# 06_LMS7002M_Power.net
KiCad netlist of a schematic drawn in Altium Designer
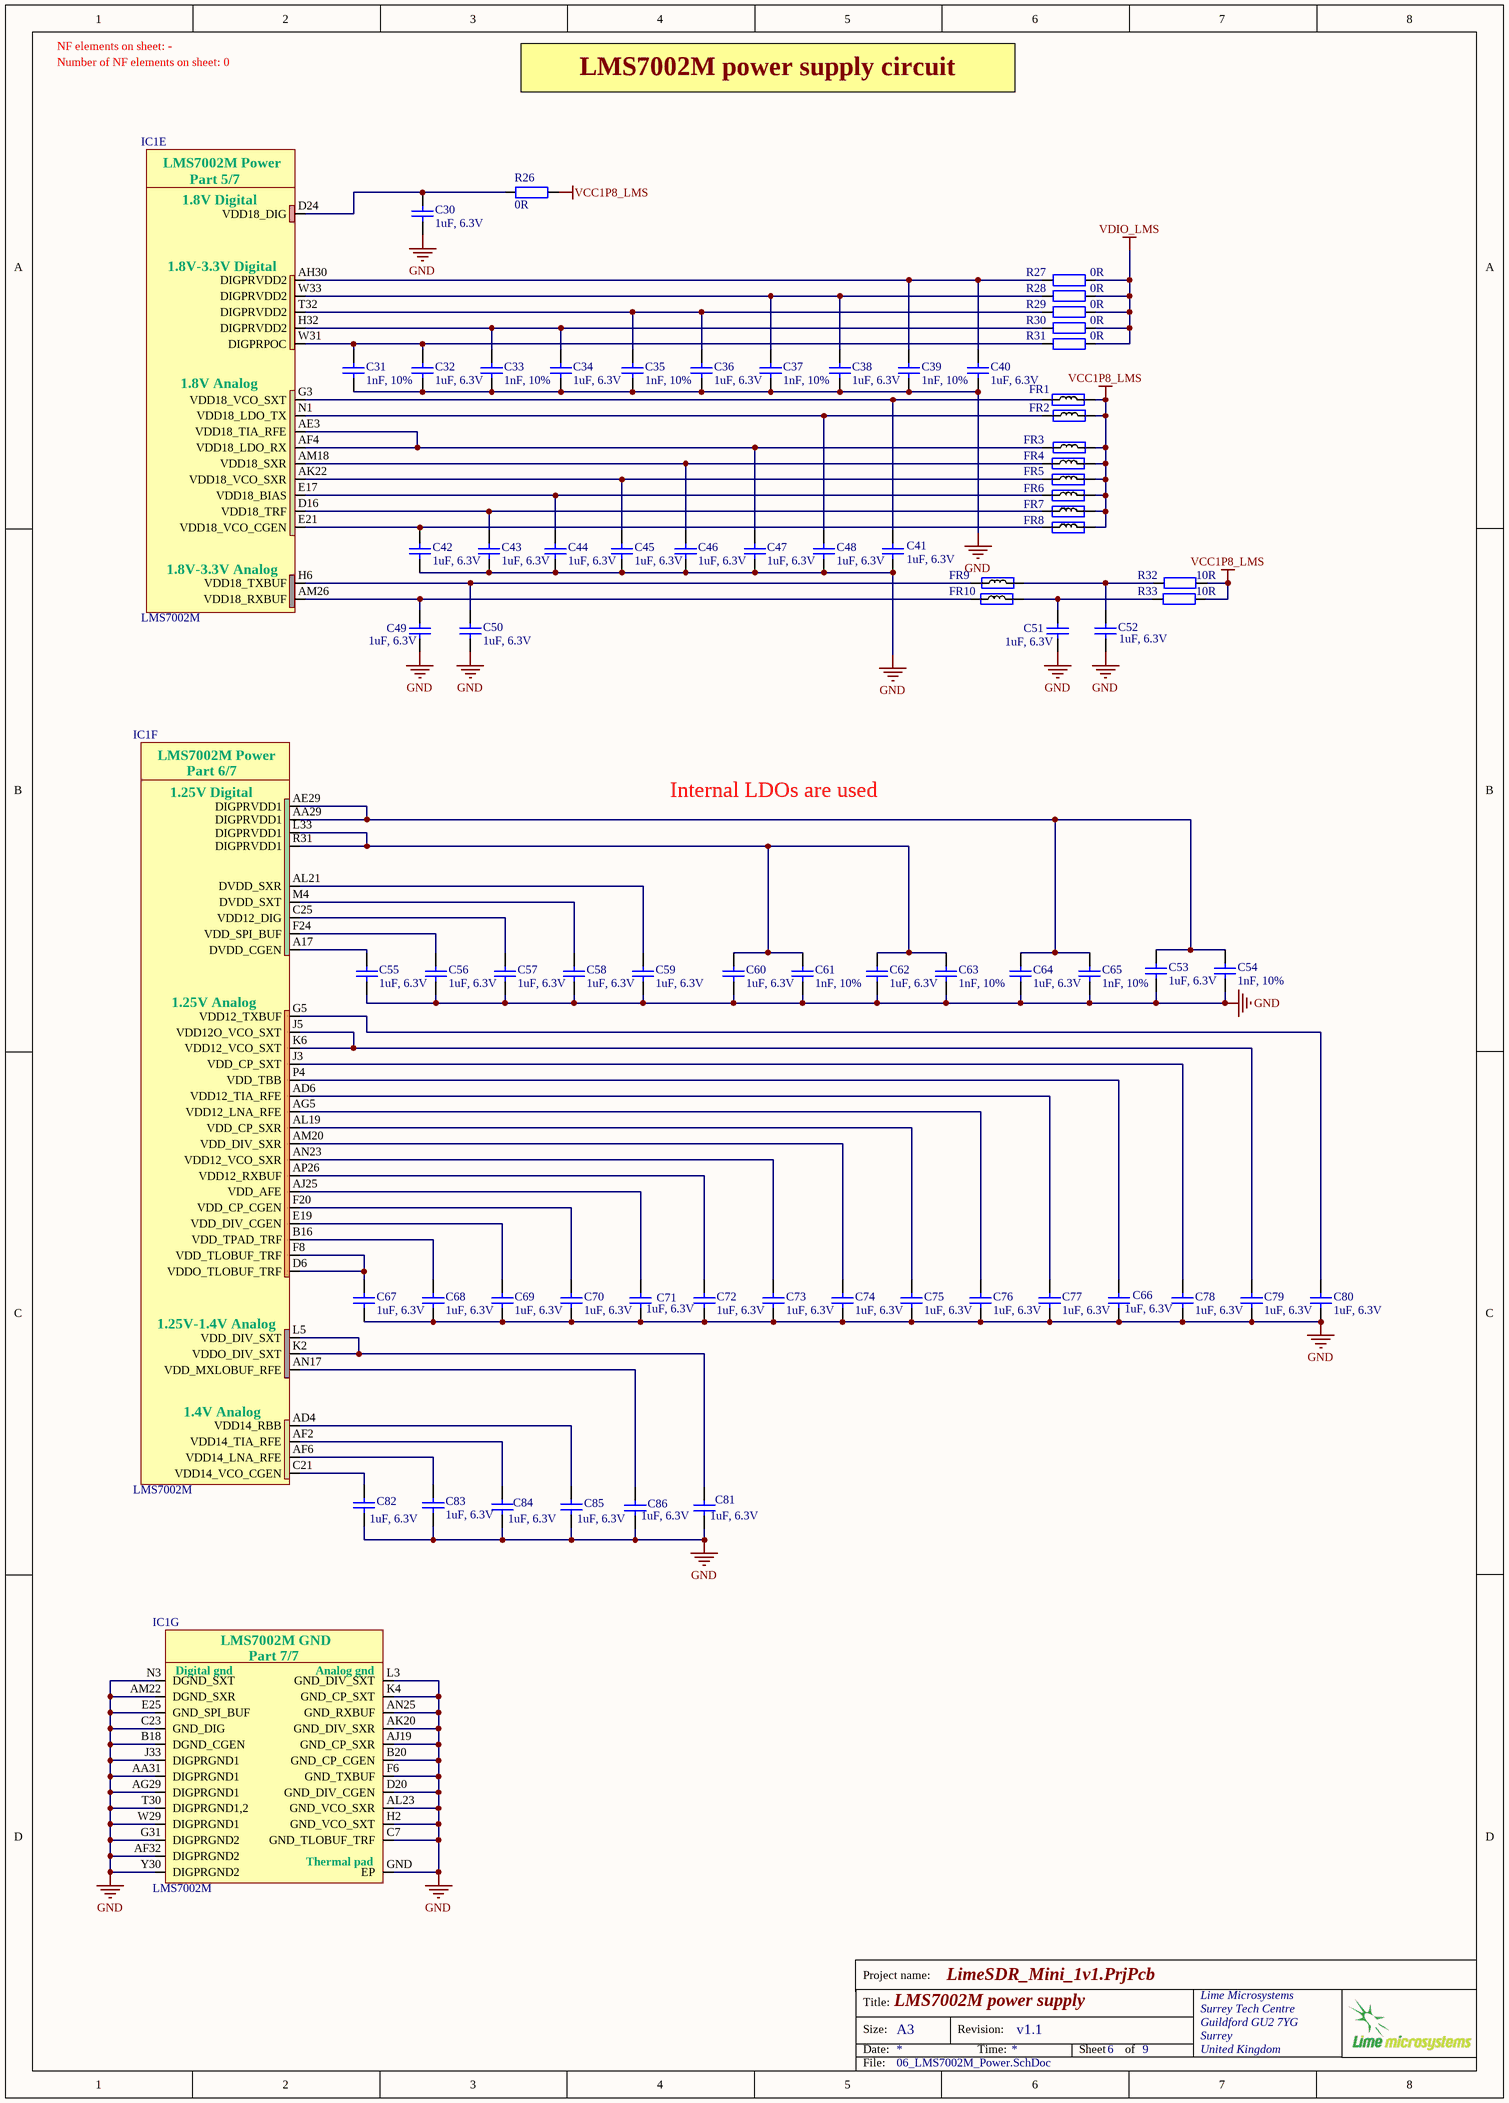
[diagram p0: 06_LMS7002M_Power.SchDoc]

(export (version "E")
  (design (tool "Eeschema 10.0.6"))
  (components
    (comp (ref "C30")
      (value "1uF, 6.3V")
      (footprint "CAP0201")
      (fields (field (name "TOLERANCE") "±20%") (field (name "MANUFACTURER") "TDK Corporation"))
      (libsource (lib "LimeMicroAltiumLib_schLib") (part "Cap_0402"))
    )
    (comp (ref "C31")
      (value "1nF, 10%")
      (footprint "CAP0201")
      (fields (field (name "TOLERANCE") "±10%") (field (name "MANUFACTURER") "TDK Corporation"))
      (libsource (lib "LimeMicroAltiumLib_schLib") (part "Cap_0402"))
    )
    (comp (ref "C32")
      (value "1uF, 6.3V")
      (footprint "CAP0201")
      (fields (field (name "TOLERANCE") "±20%") (field (name "MANUFACTURER") "TDK Corporation"))
      (libsource (lib "LimeMicroAltiumLib_schLib") (part "Cap_0402"))
    )
    (comp (ref "C33")
      (value "1nF, 10%")
      (footprint "CAP0201")
      (fields (field (name "TOLERANCE") "±10%") (field (name "MANUFACTURER") "TDK Corporation"))
      (libsource (lib "LimeMicroAltiumLib_schLib") (part "Cap_0402"))
    )
    (comp (ref "C34")
      (value "1uF, 6.3V")
      (footprint "CAP0201")
      (fields (field (name "TOLERANCE") "±20%") (field (name "MANUFACTURER") "TDK Corporation"))
      (libsource (lib "LimeMicroAltiumLib_schLib") (part "Cap_0402"))
    )
    (comp (ref "C35")
      (value "1nF, 10%")
      (footprint "CAP0201")
      (fields (field (name "TOLERANCE") "±10%") (field (name "MANUFACTURER") "TDK Corporation"))
      (libsource (lib "LimeMicroAltiumLib_schLib") (part "Cap_0402"))
    )
    (comp (ref "C36")
      (value "1uF, 6.3V")
      (footprint "CAP0201")
      (fields (field (name "TOLERANCE") "±20%") (field (name "MANUFACTURER") "TDK Corporation"))
      (libsource (lib "LimeMicroAltiumLib_schLib") (part "Cap_0402"))
    )
    (comp (ref "C37")
      (value "1nF, 10%")
      (footprint "CAP0201")
      (fields (field (name "TOLERANCE") "±10%") (field (name "MANUFACTURER") "TDK Corporation"))
      (libsource (lib "LimeMicroAltiumLib_schLib") (part "Cap_0402"))
    )
    (comp (ref "C38")
      (value "1uF, 6.3V")
      (footprint "CAP0201")
      (fields (field (name "TOLERANCE") "±20%") (field (name "MANUFACTURER") "TDK Corporation"))
      (libsource (lib "LimeMicroAltiumLib_schLib") (part "Cap_0402"))
    )
    (comp (ref "C39")
      (value "1nF, 10%")
      (footprint "CAP0201")
      (fields (field (name "TOLERANCE") "±10%") (field (name "MANUFACTURER") "TDK Corporation"))
      (libsource (lib "LimeMicroAltiumLib_schLib") (part "Cap_0402"))
    )
    (comp (ref "C40")
      (value "1uF, 6.3V")
      (footprint "CAP0201")
      (fields (field (name "TOLERANCE") "±20%") (field (name "MANUFACTURER") "TDK Corporation"))
      (libsource (lib "LimeMicroAltiumLib_schLib") (part "Cap_0402"))
    )
    (comp (ref "C41")
      (value "1uF, 6.3V")
      (footprint "CAP0201")
      (fields (field (name "TOLERANCE") "±20%") (field (name "MANUFACTURER") "TDK Corporation"))
      (libsource (lib "LimeMicroAltiumLib_schLib") (part "Cap_0402"))
    )
    (comp (ref "C42")
      (value "1uF, 6.3V")
      (footprint "CAP0201")
      (fields (field (name "TOLERANCE") "±20%") (field (name "MANUFACTURER") "TDK Corporation"))
      (libsource (lib "LimeMicroAltiumLib_schLib") (part "Cap_0402"))
    )
    (comp (ref "C43")
      (value "1uF, 6.3V")
      (footprint "CAP0201")
      (fields (field (name "TOLERANCE") "±20%") (field (name "MANUFACTURER") "TDK Corporation"))
      (libsource (lib "LimeMicroAltiumLib_schLib") (part "Cap_0402"))
    )
    (comp (ref "C44")
      (value "1uF, 6.3V")
      (footprint "CAP0201")
      (fields (field (name "TOLERANCE") "±20%") (field (name "MANUFACTURER") "TDK Corporation"))
      (libsource (lib "LimeMicroAltiumLib_schLib") (part "Cap_0402"))
    )
    (comp (ref "C45")
      (value "1uF, 6.3V")
      (footprint "CAP0201")
      (fields (field (name "TOLERANCE") "±20%") (field (name "MANUFACTURER") "TDK Corporation"))
      (libsource (lib "LimeMicroAltiumLib_schLib") (part "Cap_0402"))
    )
    (comp (ref "C46")
      (value "1uF, 6.3V")
      (footprint "CAP0201")
      (fields (field (name "TOLERANCE") "±20%") (field (name "MANUFACTURER") "TDK Corporation"))
      (libsource (lib "LimeMicroAltiumLib_schLib") (part "Cap_0402"))
    )
    (comp (ref "C47")
      (value "1uF, 6.3V")
      (footprint "CAP0201")
      (fields (field (name "TOLERANCE") "±20%") (field (name "MANUFACTURER") "TDK Corporation"))
      (libsource (lib "LimeMicroAltiumLib_schLib") (part "Cap_0402"))
    )
    (comp (ref "C48")
      (value "1uF, 6.3V")
      (footprint "CAP0201")
      (fields (field (name "TOLERANCE") "±20%") (field (name "MANUFACTURER") "TDK Corporation"))
      (libsource (lib "LimeMicroAltiumLib_schLib") (part "Cap_0402"))
    )
    (comp (ref "C49")
      (value "1uF, 6.3V")
      (footprint "CAP0201")
      (fields (field (name "TOLERANCE") "±20%") (field (name "MANUFACTURER") "TDK Corporation"))
      (libsource (lib "LimeMicroAltiumLib_schLib") (part "Cap_0402"))
    )
    (comp (ref "C50")
      (value "1uF, 6.3V")
      (footprint "CAP0201")
      (fields (field (name "TOLERANCE") "±20%") (field (name "MANUFACTURER") "TDK Corporation"))
      (libsource (lib "LimeMicroAltiumLib_schLib") (part "Cap_0402"))
    )
    (comp (ref "C51")
      (value "1uF, 6.3V")
      (footprint "CAP0201")
      (fields (field (name "TOLERANCE") "±20%") (field (name "MANUFACTURER") "TDK Corporation"))
      (libsource (lib "LimeMicroAltiumLib_schLib") (part "Cap_0402"))
    )
    (comp (ref "C52")
      (value "1uF, 6.3V")
      (footprint "CAP0201")
      (fields (field (name "TOLERANCE") "±20%") (field (name "MANUFACTURER") "TDK Corporation"))
      (libsource (lib "LimeMicroAltiumLib_schLib") (part "Cap_0402"))
    )
    (comp (ref "C53")
      (value "1uF, 6.3V")
      (footprint "CAP0201")
      (fields (field (name "TOLERANCE") "±20%") (field (name "MANUFACTURER") "TDK Corporation"))
      (libsource (lib "LimeMicroAltiumLib_schLib") (part "Cap_0402"))
    )
    (comp (ref "C54")
      (value "1nF, 10%")
      (footprint "CAP0201")
      (fields (field (name "TOLERANCE") "±10%") (field (name "MANUFACTURER") "TDK Corporation"))
      (libsource (lib "LimeMicroAltiumLib_schLib") (part "Cap_0402"))
    )
    (comp (ref "C55")
      (value "1uF, 6.3V")
      (footprint "CAP0201")
      (fields (field (name "TOLERANCE") "±20%") (field (name "MANUFACTURER") "TDK Corporation"))
      (libsource (lib "LimeMicroAltiumLib_schLib") (part "Cap_0402"))
    )
    (comp (ref "C56")
      (value "1uF, 6.3V")
      (footprint "CAP0201")
      (fields (field (name "TOLERANCE") "±20%") (field (name "MANUFACTURER") "TDK Corporation"))
      (libsource (lib "LimeMicroAltiumLib_schLib") (part "Cap_0402"))
    )
    (comp (ref "C57")
      (value "1uF, 6.3V")
      (footprint "CAP0201")
      (fields (field (name "TOLERANCE") "±20%") (field (name "MANUFACTURER") "TDK Corporation"))
      (libsource (lib "LimeMicroAltiumLib_schLib") (part "Cap_0402"))
    )
    (comp (ref "C58")
      (value "1uF, 6.3V")
      (footprint "CAP0201")
      (fields (field (name "TOLERANCE") "±20%") (field (name "MANUFACTURER") "TDK Corporation"))
      (libsource (lib "LimeMicroAltiumLib_schLib") (part "Cap_0402"))
    )
    (comp (ref "C59")
      (value "1uF, 6.3V")
      (footprint "CAP0201")
      (fields (field (name "TOLERANCE") "±20%") (field (name "MANUFACTURER") "TDK Corporation"))
      (libsource (lib "LimeMicroAltiumLib_schLib") (part "Cap_0402"))
    )
    (comp (ref "C60")
      (value "1uF, 6.3V")
      (footprint "CAP0201")
      (fields (field (name "TOLERANCE") "±20%") (field (name "MANUFACTURER") "TDK Corporation"))
      (libsource (lib "LimeMicroAltiumLib_schLib") (part "Cap_0402"))
    )
    (comp (ref "C61")
      (value "1nF, 10%")
      (footprint "CAP0201")
      (fields (field (name "TOLERANCE") "±10%") (field (name "MANUFACTURER") "TDK Corporation"))
      (libsource (lib "LimeMicroAltiumLib_schLib") (part "Cap_0402"))
    )
    (comp (ref "C62")
      (value "1uF, 6.3V")
      (footprint "CAP0201")
      (fields (field (name "TOLERANCE") "±20%") (field (name "MANUFACTURER") "TDK Corporation"))
      (libsource (lib "LimeMicroAltiumLib_schLib") (part "Cap_0402"))
    )
    (comp (ref "C63")
      (value "1nF, 10%")
      (footprint "CAP0201")
      (fields (field (name "TOLERANCE") "±10%") (field (name "MANUFACTURER") "TDK Corporation"))
      (libsource (lib "LimeMicroAltiumLib_schLib") (part "Cap_0402"))
    )
    (comp (ref "C64")
      (value "1uF, 6.3V")
      (footprint "CAP0201")
      (fields (field (name "TOLERANCE") "±20%") (field (name "MANUFACTURER") "TDK Corporation"))
      (libsource (lib "LimeMicroAltiumLib_schLib") (part "Cap_0402"))
    )
    (comp (ref "C65")
      (value "1nF, 10%")
      (footprint "CAP0201")
      (fields (field (name "TOLERANCE") "±10%") (field (name "MANUFACTURER") "TDK Corporation"))
      (libsource (lib "LimeMicroAltiumLib_schLib") (part "Cap_0402"))
    )
    (comp (ref "C66")
      (value "1uF, 6.3V")
      (footprint "CAP0201")
      (fields (field (name "TOLERANCE") "±20%") (field (name "MANUFACTURER") "TDK Corporation"))
      (libsource (lib "LimeMicroAltiumLib_schLib") (part "Cap_0402"))
    )
    (comp (ref "C67")
      (value "1uF, 6.3V")
      (footprint "CAP0201")
      (fields (field (name "TOLERANCE") "±20%") (field (name "MANUFACTURER") "TDK Corporation"))
      (libsource (lib "LimeMicroAltiumLib_schLib") (part "Cap_0402"))
    )
    (comp (ref "C68")
      (value "1uF, 6.3V")
      (footprint "CAP0201")
      (fields (field (name "TOLERANCE") "±20%") (field (name "MANUFACTURER") "TDK Corporation"))
      (libsource (lib "LimeMicroAltiumLib_schLib") (part "Cap_0402"))
    )
    (comp (ref "C69")
      (value "1uF, 6.3V")
      (footprint "CAP0201")
      (fields (field (name "TOLERANCE") "±20%") (field (name "MANUFACTURER") "TDK Corporation"))
      (libsource (lib "LimeMicroAltiumLib_schLib") (part "Cap_0402"))
    )
    (comp (ref "C70")
      (value "1uF, 6.3V")
      (footprint "CAP0201")
      (fields (field (name "TOLERANCE") "±20%") (field (name "MANUFACTURER") "TDK Corporation"))
      (libsource (lib "LimeMicroAltiumLib_schLib") (part "Cap_0402"))
    )
    (comp (ref "C71")
      (value "1uF, 6.3V")
      (footprint "CAP0201")
      (fields (field (name "TOLERANCE") "±20%") (field (name "MANUFACTURER") "TDK Corporation"))
      (libsource (lib "LimeMicroAltiumLib_schLib") (part "Cap_0402"))
    )
    (comp (ref "C72")
      (value "1uF, 6.3V")
      (footprint "CAP0201")
      (fields (field (name "TOLERANCE") "±20%") (field (name "MANUFACTURER") "TDK Corporation"))
      (libsource (lib "LimeMicroAltiumLib_schLib") (part "Cap_0402"))
    )
    (comp (ref "C73")
      (value "1uF, 6.3V")
      (footprint "CAP0201")
      (fields (field (name "TOLERANCE") "±20%") (field (name "MANUFACTURER") "TDK Corporation"))
      (libsource (lib "LimeMicroAltiumLib_schLib") (part "Cap_0402"))
    )
    (comp (ref "C74")
      (value "1uF, 6.3V")
      (footprint "CAP0201")
      (fields (field (name "TOLERANCE") "±20%") (field (name "MANUFACTURER") "TDK Corporation"))
      (libsource (lib "LimeMicroAltiumLib_schLib") (part "Cap_0402"))
    )
    (comp (ref "C75")
      (value "1uF, 6.3V")
      (footprint "CAP0201")
      (fields (field (name "TOLERANCE") "±20%") (field (name "MANUFACTURER") "TDK Corporation"))
      (libsource (lib "LimeMicroAltiumLib_schLib") (part "Cap_0402"))
    )
    (comp (ref "C76")
      (value "1uF, 6.3V")
      (footprint "CAP0201")
      (fields (field (name "TOLERANCE") "±20%") (field (name "MANUFACTURER") "TDK Corporation"))
      (libsource (lib "LimeMicroAltiumLib_schLib") (part "Cap_0402"))
    )
    (comp (ref "C77")
      (value "1uF, 6.3V")
      (footprint "CAP0201")
      (fields (field (name "TOLERANCE") "±20%") (field (name "MANUFACTURER") "TDK Corporation"))
      (libsource (lib "LimeMicroAltiumLib_schLib") (part "Cap_0402"))
    )
    (comp (ref "C78")
      (value "1uF, 6.3V")
      (footprint "CAP0201")
      (fields (field (name "TOLERANCE") "±20%") (field (name "MANUFACTURER") "TDK Corporation"))
      (libsource (lib "LimeMicroAltiumLib_schLib") (part "Cap_0402"))
    )
    (comp (ref "C79")
      (value "1uF, 6.3V")
      (footprint "CAP0201")
      (fields (field (name "TOLERANCE") "±20%") (field (name "MANUFACTURER") "TDK Corporation"))
      (libsource (lib "LimeMicroAltiumLib_schLib") (part "Cap_0402"))
    )
    (comp (ref "C80")
      (value "1uF, 6.3V")
      (footprint "CAP0201")
      (fields (field (name "TOLERANCE") "±20%") (field (name "MANUFACTURER") "TDK Corporation"))
      (libsource (lib "LimeMicroAltiumLib_schLib") (part "Cap_0402"))
    )
    (comp (ref "C81")
      (value "1uF, 6.3V")
      (footprint "CAP0201")
      (fields (field (name "TOLERANCE") "±20%") (field (name "MANUFACTURER") "TDK Corporation"))
      (libsource (lib "LimeMicroAltiumLib_schLib") (part "Cap_0402"))
    )
    (comp (ref "C82")
      (value "1uF, 6.3V")
      (footprint "CAP0201")
      (fields (field (name "TOLERANCE") "±20%") (field (name "MANUFACTURER") "TDK Corporation"))
      (libsource (lib "LimeMicroAltiumLib_schLib") (part "Cap_0402"))
    )
    (comp (ref "C83")
      (value "1uF, 6.3V")
      (footprint "CAP0201")
      (fields (field (name "TOLERANCE") "±20%") (field (name "MANUFACTURER") "TDK Corporation"))
      (libsource (lib "LimeMicroAltiumLib_schLib") (part "Cap_0402"))
    )
    (comp (ref "C84")
      (value "1uF, 6.3V")
      (footprint "CAP0201")
      (fields (field (name "TOLERANCE") "±20%") (field (name "MANUFACTURER") "TDK Corporation"))
      (libsource (lib "LimeMicroAltiumLib_schLib") (part "Cap_0402"))
    )
    (comp (ref "C85")
      (value "1uF, 6.3V")
      (footprint "CAP0201")
      (fields (field (name "TOLERANCE") "±20%") (field (name "MANUFACTURER") "TDK Corporation"))
      (libsource (lib "LimeMicroAltiumLib_schLib") (part "Cap_0402"))
    )
    (comp (ref "C86")
      (value "1uF, 6.3V")
      (footprint "CAP0201")
      (fields (field (name "TOLERANCE") "±20%") (field (name "MANUFACTURER") "TDK Corporation"))
      (libsource (lib "LimeMicroAltiumLib_schLib") (part "Cap_0402"))
    )
    (comp (ref "FR1")
      (value "600R, 0.27A")
      (footprint "RES0201")
      (fields (field (name "MANUFACTURER") "Taiyo Yuden"))
      (libsource (lib "LimeMicroAltiumLib_schLib") (part "Ferrite"))
    )
    (comp (ref "FR2")
      (value "600R, 0.27A")
      (footprint "RES0201")
      (fields (field (name "MANUFACTURER") "Taiyo Yuden"))
      (libsource (lib "") (part "Ferrite_1"))
    )
    (comp (ref "FR3")
      (value "600R, 0.27A")
      (footprint "RES0201")
      (fields (field (name "MANUFACTURER") "Taiyo Yuden"))
      (libsource (lib "") (part "Ferrite_1"))
    )
    (comp (ref "FR4")
      (value "600R, 0.27A")
      (footprint "RES0201")
      (fields (field (name "MANUFACTURER") "Taiyo Yuden"))
      (libsource (lib "LimeMicroAltiumLib_schLib") (part "Ferrite"))
    )
    (comp (ref "FR5")
      (value "600R, 0.27A")
      (footprint "RES0201")
      (fields (field (name "MANUFACTURER") "Taiyo Yuden"))
      (libsource (lib "LimeMicroAltiumLib_schLib") (part "Ferrite"))
    )
    (comp (ref "FR6")
      (value "600R, 0.27A")
      (footprint "RES0201")
      (fields (field (name "MANUFACTURER") "Taiyo Yuden"))
      (libsource (lib "LimeMicroAltiumLib_schLib") (part "Ferrite"))
    )
    (comp (ref "FR7")
      (value "600R, 0.27A")
      (footprint "RES0201")
      (fields (field (name "MANUFACTURER") "Taiyo Yuden"))
      (libsource (lib "LimeMicroAltiumLib_schLib") (part "Ferrite"))
    )
    (comp (ref "FR8")
      (value "600R, 0.27A")
      (footprint "RES0201")
      (fields (field (name "MANUFACTURER") "Taiyo Yuden"))
      (libsource (lib "LimeMicroAltiumLib_schLib") (part "Ferrite"))
    )
    (comp (ref "FR9")
      (value "600R, 0.27A")
      (footprint "RES0201")
      (fields (field (name "MANUFACTURER") "Taiyo Yuden"))
      (libsource (lib "") (part "Ferrite_1"))
    )
    (comp (ref "FR10")
      (value "600R, 0.27A")
      (footprint "RES0201")
      (fields (field (name "MANUFACTURER") "Taiyo Yuden"))
      (libsource (lib "LimeMicroAltiumLib_schLib") (part "Ferrite"))
    )
    (comp (ref "IC1")
      (value "LMS7002M")
      (footprint "LMS7002M_v5_1")
      (description "Schematic symbol revision 3. Default footprint - 0.31mm pad")
      (fields (field (name "MANUFACTURER") "Lime Microsystems"))
      (libsource (lib "LimeMicroAltiumLib_schLib") (part "LMS7002Mr3"))
    )
    (comp (ref "R26")
      (value "0R")
      (footprint "RES0201")
      (fields (field (name "MANUFACTURER") "Rohm Semiconductor") (field (name "TOLERANCE") "Jumper"))
      (libsource (lib "LimeMicroAltiumLib_schLib") (part "Res_0402"))
    )
    (comp (ref "R27")
      (value "0R")
      (footprint "RES0402")
      (fields (field (name "MANUFACTURER") "Yageo") (field (name "TOLERANCE") "Jumper"))
      (libsource (lib "LimeMicroAltiumLib_schLib") (part "Res_0402"))
    )
    (comp (ref "R28")
      (value "0R")
      (footprint "RES0402")
      (fields (field (name "MANUFACTURER") "Yageo") (field (name "TOLERANCE") "Jumper"))
      (libsource (lib "LimeMicroAltiumLib_schLib") (part "Res_0402"))
    )
    (comp (ref "R29")
      (value "0R")
      (footprint "RES0402")
      (fields (field (name "MANUFACTURER") "Yageo") (field (name "TOLERANCE") "Jumper"))
      (libsource (lib "LimeMicroAltiumLib_schLib") (part "Res_0402"))
    )
    (comp (ref "R30")
      (value "0R")
      (footprint "RES0402")
      (fields (field (name "MANUFACTURER") "Yageo") (field (name "TOLERANCE") "Jumper"))
      (libsource (lib "LimeMicroAltiumLib_schLib") (part "Res_0402"))
    )
    (comp (ref "R31")
      (value "0R")
      (footprint "RES0402")
      (fields (field (name "MANUFACTURER") "Yageo") (field (name "TOLERANCE") "Jumper"))
      (libsource (lib "LimeMicroAltiumLib_schLib") (part "Res_0402"))
    )
    (comp (ref "R32")
      (value "10R")
      (footprint "RES0201")
      (fields
        (field (name "MANUFACTURER") "Panasonic Electronic Components")
        (field (name "TOLERANCE") "±1%")
        (field (name "MANUFACTURER PART NUMBER") "ERJ-1GEF10R0C")
      )
      (libsource (lib "LimeMicroAltiumLib_schLib") (part "Res_0402"))
    )
    (comp (ref "R33")
      (value "10R")
      (footprint "RES0201")
      (fields
        (field (name "MANUFACTURER") "Panasonic Electronic Components")
        (field (name "TOLERANCE") "±1%")
        (field (name "MANUFACTURER PART NUMBER") "ERJ-1GEF10R0C")
      )
      (libsource (lib "LimeMicroAltiumLib_schLib") (part "Res_0402"))
    )
  )
  (nets
    (net (code "1") (name "GND") (class "Default")
      (node (ref "C30") (pin "2") (pinfunction "2_2") (pintype "passive"))
      (node (ref "C31") (pin "2") (pinfunction "2_2") (pintype "passive"))
      (node (ref "C32") (pin "2") (pinfunction "2_2") (pintype "passive"))
      (node (ref "C33") (pin "2") (pinfunction "2_2") (pintype "passive"))
      (node (ref "C34") (pin "2") (pinfunction "2_2") (pintype "passive"))
      (node (ref "C35") (pin "2") (pinfunction "2_2") (pintype "passive"))
      (node (ref "C36") (pin "2") (pinfunction "2_2") (pintype "passive"))
      (node (ref "C37") (pin "2") (pinfunction "2_2") (pintype "passive"))
      (node (ref "C38") (pin "2") (pinfunction "2_2") (pintype "passive"))
      (node (ref "C39") (pin "2") (pinfunction "2_2") (pintype "passive"))
      (node (ref "C40") (pin "2") (pinfunction "2_2") (pintype "passive"))
      (node (ref "C41") (pin "2") (pinfunction "2_2") (pintype "passive"))
      (node (ref "C42") (pin "2") (pinfunction "2_2") (pintype "passive"))
      (node (ref "C43") (pin "2") (pinfunction "2_2") (pintype "passive"))
      (node (ref "C44") (pin "2") (pinfunction "2_2") (pintype "passive"))
      (node (ref "C45") (pin "2") (pinfunction "2_2") (pintype "passive"))
      (node (ref "C46") (pin "2") (pinfunction "2_2") (pintype "passive"))
      (node (ref "C47") (pin "2") (pinfunction "2_2") (pintype "passive"))
      (node (ref "C48") (pin "2") (pinfunction "2_2") (pintype "passive"))
      (node (ref "C49") (pin "2") (pinfunction "2_2") (pintype "passive"))
      (node (ref "C50") (pin "2") (pinfunction "2_2") (pintype "passive"))
      (node (ref "C51") (pin "2") (pinfunction "2_2") (pintype "passive"))
      (node (ref "C52") (pin "2") (pinfunction "2_2") (pintype "passive"))
      (node (ref "C53") (pin "2") (pinfunction "2_2") (pintype "passive"))
      (node (ref "C54") (pin "2") (pinfunction "2_2") (pintype "passive"))
      (node (ref "C55") (pin "2") (pinfunction "2_2") (pintype "passive"))
      (node (ref "C56") (pin "2") (pinfunction "2_2") (pintype "passive"))
      (node (ref "C57") (pin "2") (pinfunction "2_2") (pintype "passive"))
      (node (ref "C58") (pin "1") (pinfunction "1_1") (pintype "passive"))
      (node (ref "C59") (pin "2") (pinfunction "2_2") (pintype "passive"))
      (node (ref "C60") (pin "2") (pinfunction "2_2") (pintype "passive"))
      (node (ref "C61") (pin "2") (pinfunction "2_2") (pintype "passive"))
      (node (ref "C62") (pin "2") (pinfunction "2_2") (pintype "passive"))
      (node (ref "C63") (pin "2") (pinfunction "2_2") (pintype "passive"))
      (node (ref "C64") (pin "2") (pinfunction "2_2") (pintype "passive"))
      (node (ref "C65") (pin "2") (pinfunction "2_2") (pintype "passive"))
      (node (ref "C66") (pin "2") (pinfunction "2_2") (pintype "passive"))
      (node (ref "C67") (pin "2") (pinfunction "2_2") (pintype "passive"))
      (node (ref "C68") (pin "2") (pinfunction "2_2") (pintype "passive"))
      (node (ref "C69") (pin "2") (pinfunction "2_2") (pintype "passive"))
      (node (ref "C70") (pin "1") (pinfunction "1_1") (pintype "passive"))
      (node (ref "C71") (pin "2") (pinfunction "2_2") (pintype "passive"))
      (node (ref "C72") (pin "2") (pinfunction "2_2") (pintype "passive"))
      (node (ref "C73") (pin "2") (pinfunction "2_2") (pintype "passive"))
      (node (ref "C74") (pin "2") (pinfunction "2_2") (pintype "passive"))
      (node (ref "C75") (pin "2") (pinfunction "2_2") (pintype "passive"))
      (node (ref "C76") (pin "2") (pinfunction "2_2") (pintype "passive"))
      (node (ref "C77") (pin "1") (pinfunction "1_1") (pintype "passive"))
      (node (ref "C78") (pin "2") (pinfunction "2_2") (pintype "passive"))
      (node (ref "C79") (pin "1") (pinfunction "1_1") (pintype "passive"))
      (node (ref "C80") (pin "2") (pinfunction "2_2") (pintype "passive"))
      (node (ref "C81") (pin "2") (pinfunction "2_2") (pintype "passive"))
      (node (ref "C82") (pin "2") (pinfunction "2_2") (pintype "passive"))
      (node (ref "C83") (pin "2") (pinfunction "2_2") (pintype "passive"))
      (node (ref "C84") (pin "2") (pinfunction "2_2") (pintype "passive"))
      (node (ref "C85") (pin "2") (pinfunction "2_2") (pintype "passive"))
      (node (ref "C86") (pin "2") (pinfunction "2_2") (pintype "passive"))
      (node (ref "IC1") (pin "AA31") (pinfunction "DIGPRGND1_AA31") (pintype "passive"))
      (node (ref "IC1") (pin "AF32") (pinfunction "DIGPRGND2_AF32") (pintype "passive"))
      (node (ref "IC1") (pin "AG29") (pinfunction "DIGPRGND1_AG29") (pintype "passive"))
      (node (ref "IC1") (pin "AJ19") (pinfunction "GND_CP_SXR_AJ19") (pintype "passive"))
      (node (ref "IC1") (pin "AK20") (pinfunction "GND_DIV_SXR_AK20") (pintype "passive"))
      (node (ref "IC1") (pin "AL23") (pinfunction "GND_VCO_SXR_AL23") (pintype "passive"))
      (node (ref "IC1") (pin "AM22") (pinfunction "DGND_SXR_AM22") (pintype "passive"))
      (node (ref "IC1") (pin "AN25") (pinfunction "GND_RXBUF_AN25") (pintype "passive"))
      (node (ref "IC1") (pin "B18") (pinfunction "DGND_CGEN_B18") (pintype "passive"))
      (node (ref "IC1") (pin "B20") (pinfunction "GND_CP_CGEN_B20") (pintype "passive"))
      (node (ref "IC1") (pin "C23") (pinfunction "GND_DIG_C23") (pintype "passive"))
      (node (ref "IC1") (pin "C7") (pinfunction "GND_TLOBUF_TRF_C7") (pintype "passive"))
      (node (ref "IC1") (pin "D20") (pinfunction "GND_DIV_CGEN_D20") (pintype "passive"))
      (node (ref "IC1") (pin "E25") (pinfunction "GND_SPI_BUF_E25") (pintype "passive"))
      (node (ref "IC1") (pin "F6") (pinfunction "GND_TXBUF_F6") (pintype "passive"))
      (node (ref "IC1") (pin "G31") (pinfunction "DIGPRGND2_G31") (pintype "passive"))
      (node (ref "IC1") (pin "GND") (pinfunction "EP_GND") (pintype "passive"))
      (node (ref "IC1") (pin "H2") (pinfunction "GND_VCO_SXT_H2") (pintype "passive"))
      (node (ref "IC1") (pin "J33") (pinfunction "DIGPRGND1_J33") (pintype "passive"))
      (node (ref "IC1") (pin "K4") (pinfunction "GND_CP_SXT_K4") (pintype "passive"))
      (node (ref "IC1") (pin "L3") (pinfunction "GND_DIV_SXT_L3") (pintype "passive"))
      (node (ref "IC1") (pin "N3") (pinfunction "DGND_SXT_N3") (pintype "passive"))
      (node (ref "IC1") (pin "T30") (pinfunction "DIGPRGND1,2_T30") (pintype "passive"))
      (node (ref "IC1") (pin "W29") (pinfunction "DIGPRGND1_W29") (pintype "passive"))
      (node (ref "IC1") (pin "Y30") (pinfunction "DIGPRGND2_Y30") (pintype "passive"))
    )
    (net (code "2") (name "Net-(C33-Pad1)") (class "Default")
      (node (ref "C33") (pin "1") (pinfunction "1_1") (pintype "passive"))
      (node (ref "C34") (pin "1") (pinfunction "1_1") (pintype "passive"))
      (node (ref "IC1") (pin "H32") (pinfunction "DIGPRVDD2_H32") (pintype "power_in"))
      (node (ref "R30") (pin "2") (pinfunction "2_2") (pintype "passive"))
    )
    (net (code "3") (name "Net-(C35-Pad1)") (class "Default")
      (node (ref "C35") (pin "1") (pinfunction "1_1") (pintype "passive"))
      (node (ref "C36") (pin "1") (pinfunction "1_1") (pintype "passive"))
      (node (ref "IC1") (pin "T32") (pinfunction "DIGPRVDD2_T32") (pintype "power_in"))
      (node (ref "R29") (pin "2") (pinfunction "2_2") (pintype "passive"))
    )
    (net (code "4") (name "Net-(C37-Pad1)") (class "Default")
      (node (ref "C37") (pin "1") (pinfunction "1_1") (pintype "passive"))
      (node (ref "C38") (pin "1") (pinfunction "1_1") (pintype "passive"))
      (node (ref "IC1") (pin "W33") (pinfunction "DIGPRVDD2_W33") (pintype "power_in"))
      (node (ref "R28") (pin "2") (pinfunction "2_2") (pintype "passive"))
    )
    (net (code "5") (name "Net-(C39-Pad1)") (class "Default")
      (node (ref "C39") (pin "1") (pinfunction "1_1") (pintype "passive"))
      (node (ref "C40") (pin "1") (pinfunction "1_1") (pintype "passive"))
      (node (ref "IC1") (pin "AH30") (pinfunction "DIGPRVDD2_AH30") (pintype "power_in"))
      (node (ref "R27") (pin "2") (pinfunction "2_2") (pintype "passive"))
    )
    (net (code "6") (name "Net-(C51-Pad1)") (class "Default")
      (node (ref "C51") (pin "1") (pinfunction "1_1") (pintype "passive"))
      (node (ref "FR10") (pin "2") (pinfunction "2_2") (pintype "passive"))
      (node (ref "R33") (pin "2") (pinfunction "2_2") (pintype "passive"))
    )
    (net (code "7") (name "Net-(C52-Pad1)") (class "Default")
      (node (ref "C52") (pin "1") (pinfunction "1_1") (pintype "passive"))
      (node (ref "FR9") (pin "1") (pinfunction "1_1") (pintype "passive"))
      (node (ref "R32") (pin "1") (pinfunction "1_1") (pintype "passive"))
    )
    (net (code "8") (name "Net-(C53-Pad1)") (class "Default")
      (node (ref "C53") (pin "1") (pinfunction "1_1") (pintype "passive"))
      (node (ref "C54") (pin "1") (pinfunction "1_1") (pintype "passive"))
      (node (ref "C64") (pin "1") (pinfunction "1_1") (pintype "passive"))
      (node (ref "C65") (pin "1") (pinfunction "1_1") (pintype "passive"))
      (node (ref "IC1") (pin "AA29") (pinfunction "DIGPRVDD1_AA29") (pintype "power_in"))
      (node (ref "IC1") (pin "AE29") (pinfunction "DIGPRVDD1_AE29") (pintype "power_in"))
    )
    (net (code "9") (name "Net-(C60-Pad1)") (class "Default")
      (node (ref "C60") (pin "1") (pinfunction "1_1") (pintype "passive"))
      (node (ref "C61") (pin "1") (pinfunction "1_1") (pintype "passive"))
      (node (ref "C62") (pin "1") (pinfunction "1_1") (pintype "passive"))
      (node (ref "C63") (pin "1") (pinfunction "1_1") (pintype "passive"))
      (node (ref "IC1") (pin "L33") (pinfunction "DIGPRVDD1_L33") (pintype "power_in"))
      (node (ref "IC1") (pin "R31") (pinfunction "DIGPRVDD1_R31") (pintype "power_in"))
    )
    (net (code "10") (name "Net-(IC1E-DIGPRPOC)") (class "Default")
      (node (ref "C31") (pin "1") (pinfunction "1_1") (pintype "passive"))
      (node (ref "C32") (pin "1") (pinfunction "1_1") (pintype "passive"))
      (node (ref "IC1") (pin "W31") (pinfunction "DIGPRPOC_W31") (pintype "power_in"))
      (node (ref "R31") (pin "2") (pinfunction "2_2") (pintype "passive"))
    )
    (net (code "11") (name "Net-(IC1E-VDD18_BIAS)") (class "Default")
      (node (ref "C44") (pin "1") (pinfunction "1_1") (pintype "passive"))
      (node (ref "FR6") (pin "1") (pinfunction "1_1") (pintype "passive"))
      (node (ref "IC1") (pin "E17") (pinfunction "VDD18_BIAS_E17") (pintype "power_in"))
    )
    (net (code "12") (name "Net-(IC1E-VDD18_DIG)") (class "Default")
      (node (ref "C30") (pin "1") (pinfunction "1_1") (pintype "passive"))
      (node (ref "IC1") (pin "D24") (pinfunction "VDD18_DIG_D24") (pintype "power_in"))
      (node (ref "R26") (pin "1") (pinfunction "1_1") (pintype "passive"))
    )
    (net (code "13") (name "Net-(IC1E-VDD18_LDO_RX)") (class "Default")
      (node (ref "C47") (pin "1") (pinfunction "1_1") (pintype "passive"))
      (node (ref "FR3") (pin "2") (pinfunction "2_2") (pintype "passive"))
      (node (ref "IC1") (pin "AE3") (pinfunction "VDD18_TIA_RFE_AE3") (pintype "power_in"))
      (node (ref "IC1") (pin "AF4") (pinfunction "VDD18_LDO_RX_AF4") (pintype "power_in"))
    )
    (net (code "14") (name "Net-(IC1E-VDD18_LDO_TX)") (class "Default")
      (node (ref "C48") (pin "1") (pinfunction "1_1") (pintype "passive"))
      (node (ref "FR2") (pin "2") (pinfunction "2_2") (pintype "passive"))
      (node (ref "IC1") (pin "N1") (pinfunction "VDD18_LDO_TX_N1") (pintype "power_in"))
    )
    (net (code "15") (name "Net-(IC1E-VDD18_RXBUF)") (class "Default")
      (node (ref "C49") (pin "1") (pinfunction "1_1") (pintype "passive"))
      (node (ref "FR10") (pin "1") (pinfunction "1_1") (pintype "passive"))
      (node (ref "IC1") (pin "AM26") (pinfunction "VDD18_RXBUF_AM26") (pintype "power_in"))
    )
    (net (code "16") (name "Net-(IC1E-VDD18_SXR)") (class "Default")
      (node (ref "C46") (pin "1") (pinfunction "1_1") (pintype "passive"))
      (node (ref "FR4") (pin "1") (pinfunction "1_1") (pintype "passive"))
      (node (ref "IC1") (pin "AM18") (pinfunction "VDD18_SXR_AM18") (pintype "power_in"))
    )
    (net (code "17") (name "Net-(IC1E-VDD18_TRF)") (class "Default")
      (node (ref "C43") (pin "1") (pinfunction "1_1") (pintype "passive"))
      (node (ref "FR7") (pin "1") (pinfunction "1_1") (pintype "passive"))
      (node (ref "IC1") (pin "D16") (pinfunction "VDD18_TRF_D16") (pintype "power_in"))
    )
    (net (code "18") (name "Net-(IC1E-VDD18_TXBUF)") (class "Default")
      (node (ref "C50") (pin "1") (pinfunction "1_1") (pintype "passive"))
      (node (ref "FR9") (pin "2") (pinfunction "2_2") (pintype "passive"))
      (node (ref "IC1") (pin "H6") (pinfunction "VDD18_TXBUF_H6") (pintype "power_in"))
    )
    (net (code "19") (name "Net-(IC1E-VDD18_VCO_CGEN)") (class "Default")
      (node (ref "C42") (pin "1") (pinfunction "1_1") (pintype "passive"))
      (node (ref "FR8") (pin "1") (pinfunction "1_1") (pintype "passive"))
      (node (ref "IC1") (pin "E21") (pinfunction "VDD18_VCO_CGEN_E21") (pintype "power_in"))
    )
    (net (code "20") (name "Net-(IC1E-VDD18_VCO_SXR)") (class "Default")
      (node (ref "C45") (pin "1") (pinfunction "1_1") (pintype "passive"))
      (node (ref "FR5") (pin "1") (pinfunction "1_1") (pintype "passive"))
      (node (ref "IC1") (pin "AK22") (pinfunction "VDD18_VCO_SXR_AK22") (pintype "power_in"))
    )
    (net (code "21") (name "Net-(IC1E-VDD18_VCO_SXT)") (class "Default")
      (node (ref "C41") (pin "1") (pinfunction "1_1") (pintype "passive"))
      (node (ref "FR1") (pin "1") (pinfunction "1_1") (pintype "passive"))
      (node (ref "IC1") (pin "G3") (pinfunction "VDD18_VCO_SXT_G3") (pintype "power_in"))
    )
    (net (code "22") (name "Net-(IC1F-DVDD_CGEN)") (class "Default")
      (node (ref "C55") (pin "1") (pinfunction "1_1") (pintype "passive"))
      (node (ref "IC1") (pin "A17") (pinfunction "DVDD_CGEN_A17") (pintype "power_in"))
    )
    (net (code "23") (name "Net-(IC1F-DVDD_SXR)") (class "Default")
      (node (ref "C59") (pin "1") (pinfunction "1_1") (pintype "passive"))
      (node (ref "IC1") (pin "AL21") (pinfunction "DVDD_SXR_AL21") (pintype "power_in"))
    )
    (net (code "24") (name "Net-(IC1F-DVDD_SXT)") (class "Default")
      (node (ref "C58") (pin "2") (pinfunction "2_2") (pintype "passive"))
      (node (ref "IC1") (pin "M4") (pinfunction "DVDD_SXT_M4") (pintype "power_in"))
    )
    (net (code "25") (name "Net-(IC1F-VDD12O_VCO_SXT)") (class "Default")
      (node (ref "C79") (pin "2") (pinfunction "2_2") (pintype "passive"))
      (node (ref "IC1") (pin "J5") (pinfunction "VDD12O_VCO_SXT_J5") (pintype "power_in"))
      (node (ref "IC1") (pin "K6") (pinfunction "VDD12_VCO_SXT_K6") (pintype "power_in"))
    )
    (net (code "26") (name "Net-(IC1F-VDD12_DIG)") (class "Default")
      (node (ref "C57") (pin "1") (pinfunction "1_1") (pintype "passive"))
      (node (ref "IC1") (pin "C25") (pinfunction "VDD12_DIG_C25") (pintype "power_in"))
    )
    (net (code "27") (name "Net-(IC1F-VDD12_LNA_RFE)") (class "Default")
      (node (ref "C76") (pin "1") (pinfunction "1_1") (pintype "passive"))
      (node (ref "IC1") (pin "AG5") (pinfunction "VDD12_LNA_RFE_AG5") (pintype "power_in"))
    )
    (net (code "28") (name "Net-(IC1F-VDD12_RXBUF)") (class "Default")
      (node (ref "C72") (pin "1") (pinfunction "1_1") (pintype "passive"))
      (node (ref "IC1") (pin "AP26") (pinfunction "VDD12_RXBUF_AP26") (pintype "power_in"))
    )
    (net (code "29") (name "Net-(IC1F-VDD12_TIA_RFE)") (class "Default")
      (node (ref "C77") (pin "2") (pinfunction "2_2") (pintype "passive"))
      (node (ref "IC1") (pin "AD6") (pinfunction "VDD12_TIA_RFE_AD6") (pintype "power_in"))
    )
    (net (code "30") (name "Net-(IC1F-VDD12_TXBUF)") (class "Default")
      (node (ref "C80") (pin "1") (pinfunction "1_1") (pintype "passive"))
      (node (ref "IC1") (pin "G5") (pinfunction "VDD12_TXBUF_G5") (pintype "power_in"))
    )
    (net (code "31") (name "Net-(IC1F-VDD12_VCO_SXR)") (class "Default")
      (node (ref "C73") (pin "1") (pinfunction "1_1") (pintype "passive"))
      (node (ref "IC1") (pin "AN23") (pinfunction "VDD12_VCO_SXR_AN23") (pintype "power_in"))
    )
    (net (code "32") (name "Net-(IC1F-VDD14_LNA_RFE)") (class "Default")
      (node (ref "C83") (pin "1") (pinfunction "1_1") (pintype "passive"))
      (node (ref "IC1") (pin "AF6") (pinfunction "VDD14_LNA_RFE_AF6") (pintype "power_in"))
    )
    (net (code "33") (name "Net-(IC1F-VDD14_RBB)") (class "Default")
      (node (ref "C85") (pin "1") (pinfunction "1_1") (pintype "passive"))
      (node (ref "IC1") (pin "AD4") (pinfunction "VDD14_RBB_AD4") (pintype "power_in"))
    )
    (net (code "34") (name "Net-(IC1F-VDD14_TIA_RFE)") (class "Default")
      (node (ref "C84") (pin "1") (pinfunction "1_1") (pintype "passive"))
      (node (ref "IC1") (pin "AF2") (pinfunction "VDD14_TIA_RFE_AF2") (pintype "power_in"))
    )
    (net (code "35") (name "Net-(IC1F-VDD14_VCO_CGEN)") (class "Default")
      (node (ref "C82") (pin "1") (pinfunction "1_1") (pintype "passive"))
      (node (ref "IC1") (pin "C21") (pinfunction "VDD14_VCO_CGEN_C21") (pintype "power_in"))
    )
    (net (code "36") (name "Net-(IC1F-VDDO_DIV_SXT)") (class "Default")
      (node (ref "C81") (pin "1") (pinfunction "1_1") (pintype "passive"))
      (node (ref "IC1") (pin "K2") (pinfunction "VDDO_DIV_SXT_K2") (pintype "power_in"))
      (node (ref "IC1") (pin "L5") (pinfunction "VDD_DIV_SXT_L5") (pintype "power_in"))
    )
    (net (code "37") (name "Net-(IC1F-VDDO_TLOBUF_TRF)") (class "Default")
      (node (ref "C67") (pin "1") (pinfunction "1_1") (pintype "passive"))
      (node (ref "IC1") (pin "D6") (pinfunction "VDDO_TLOBUF_TRF_D6") (pintype "power_in"))
      (node (ref "IC1") (pin "F8") (pinfunction "VDD_TLOBUF_TRF_F8") (pintype "power_in"))
    )
    (net (code "38") (name "Net-(IC1F-VDD_AFE)") (class "Default")
      (node (ref "C71") (pin "1") (pinfunction "1_1") (pintype "passive"))
      (node (ref "IC1") (pin "AJ25") (pinfunction "VDD_AFE_AJ25") (pintype "power_in"))
    )
    (net (code "39") (name "Net-(IC1F-VDD_CP_CGEN)") (class "Default")
      (node (ref "C70") (pin "2") (pinfunction "2_2") (pintype "passive"))
      (node (ref "IC1") (pin "F20") (pinfunction "VDD_CP_CGEN_F20") (pintype "power_in"))
    )
    (net (code "40") (name "Net-(IC1F-VDD_CP_SXR)") (class "Default")
      (node (ref "C75") (pin "1") (pinfunction "1_1") (pintype "passive"))
      (node (ref "IC1") (pin "AL19") (pinfunction "VDD_CP_SXR_AL19") (pintype "power_in"))
    )
    (net (code "41") (name "Net-(IC1F-VDD_CP_SXT)") (class "Default")
      (node (ref "C78") (pin "1") (pinfunction "1_1") (pintype "passive"))
      (node (ref "IC1") (pin "J3") (pinfunction "VDD_CP_SXT_J3") (pintype "power_in"))
    )
    (net (code "42") (name "Net-(IC1F-VDD_DIV_CGEN)") (class "Default")
      (node (ref "C69") (pin "1") (pinfunction "1_1") (pintype "passive"))
      (node (ref "IC1") (pin "E19") (pinfunction "VDD_DIV_CGEN_E19") (pintype "power_in"))
    )
    (net (code "43") (name "Net-(IC1F-VDD_DIV_SXR)") (class "Default")
      (node (ref "C74") (pin "1") (pinfunction "1_1") (pintype "passive"))
      (node (ref "IC1") (pin "AM20") (pinfunction "VDD_DIV_SXR_AM20") (pintype "power_in"))
    )
    (net (code "44") (name "Net-(IC1F-VDD_MXLOBUF_RFE)") (class "Default")
      (node (ref "C86") (pin "1") (pinfunction "1_1") (pintype "passive"))
      (node (ref "IC1") (pin "AN17") (pinfunction "VDD_MXLOBUF_RFE_AN17") (pintype "power_in"))
    )
    (net (code "45") (name "Net-(IC1F-VDD_SPI_BUF)") (class "Default")
      (node (ref "C56") (pin "1") (pinfunction "1_1") (pintype "passive"))
      (node (ref "IC1") (pin "F24") (pinfunction "VDD_SPI_BUF_F24") (pintype "power_in"))
    )
    (net (code "46") (name "Net-(IC1F-VDD_TBB)") (class "Default")
      (node (ref "C66") (pin "1") (pinfunction "1_1") (pintype "passive"))
      (node (ref "IC1") (pin "P4") (pinfunction "VDD_TBB_P4") (pintype "power_in"))
    )
    (net (code "47") (name "Net-(IC1F-VDD_TPAD_TRF)") (class "Default")
      (node (ref "C68") (pin "1") (pinfunction "1_1") (pintype "passive"))
      (node (ref "IC1") (pin "B16") (pinfunction "VDD_TPAD_TRF_B16") (pintype "power_in"))
    )
    (net (code "48") (name "VCC1P8_LMS") (class "Default")
      (node (ref "FR1") (pin "2") (pinfunction "2_2") (pintype "passive"))
      (node (ref "FR2") (pin "1") (pinfunction "1_1") (pintype "passive"))
      (node (ref "FR3") (pin "1") (pinfunction "1_1") (pintype "passive"))
      (node (ref "FR4") (pin "2") (pinfunction "2_2") (pintype "passive"))
      (node (ref "FR5") (pin "2") (pinfunction "2_2") (pintype "passive"))
      (node (ref "FR6") (pin "2") (pinfunction "2_2") (pintype "passive"))
      (node (ref "FR7") (pin "2") (pinfunction "2_2") (pintype "passive"))
      (node (ref "FR8") (pin "2") (pinfunction "2_2") (pintype "passive"))
      (node (ref "R26") (pin "2") (pinfunction "2_2") (pintype "passive"))
      (node (ref "R32") (pin "2") (pinfunction "2_2") (pintype "passive"))
      (node (ref "R33") (pin "1") (pinfunction "1_1") (pintype "passive"))
    )
    (net (code "49") (name "VDIO_LMS") (class "Default")
      (node (ref "R27") (pin "1") (pinfunction "1_1") (pintype "passive"))
      (node (ref "R28") (pin "1") (pinfunction "1_1") (pintype "passive"))
      (node (ref "R29") (pin "1") (pinfunction "1_1") (pintype "passive"))
      (node (ref "R30") (pin "1") (pinfunction "1_1") (pintype "passive"))
      (node (ref "R31") (pin "1") (pinfunction "1_1") (pintype "passive"))
    )
  )
)
